# Updated_Schematic_11-13.net
KiCad netlist of a schematic drawn in EAGLE
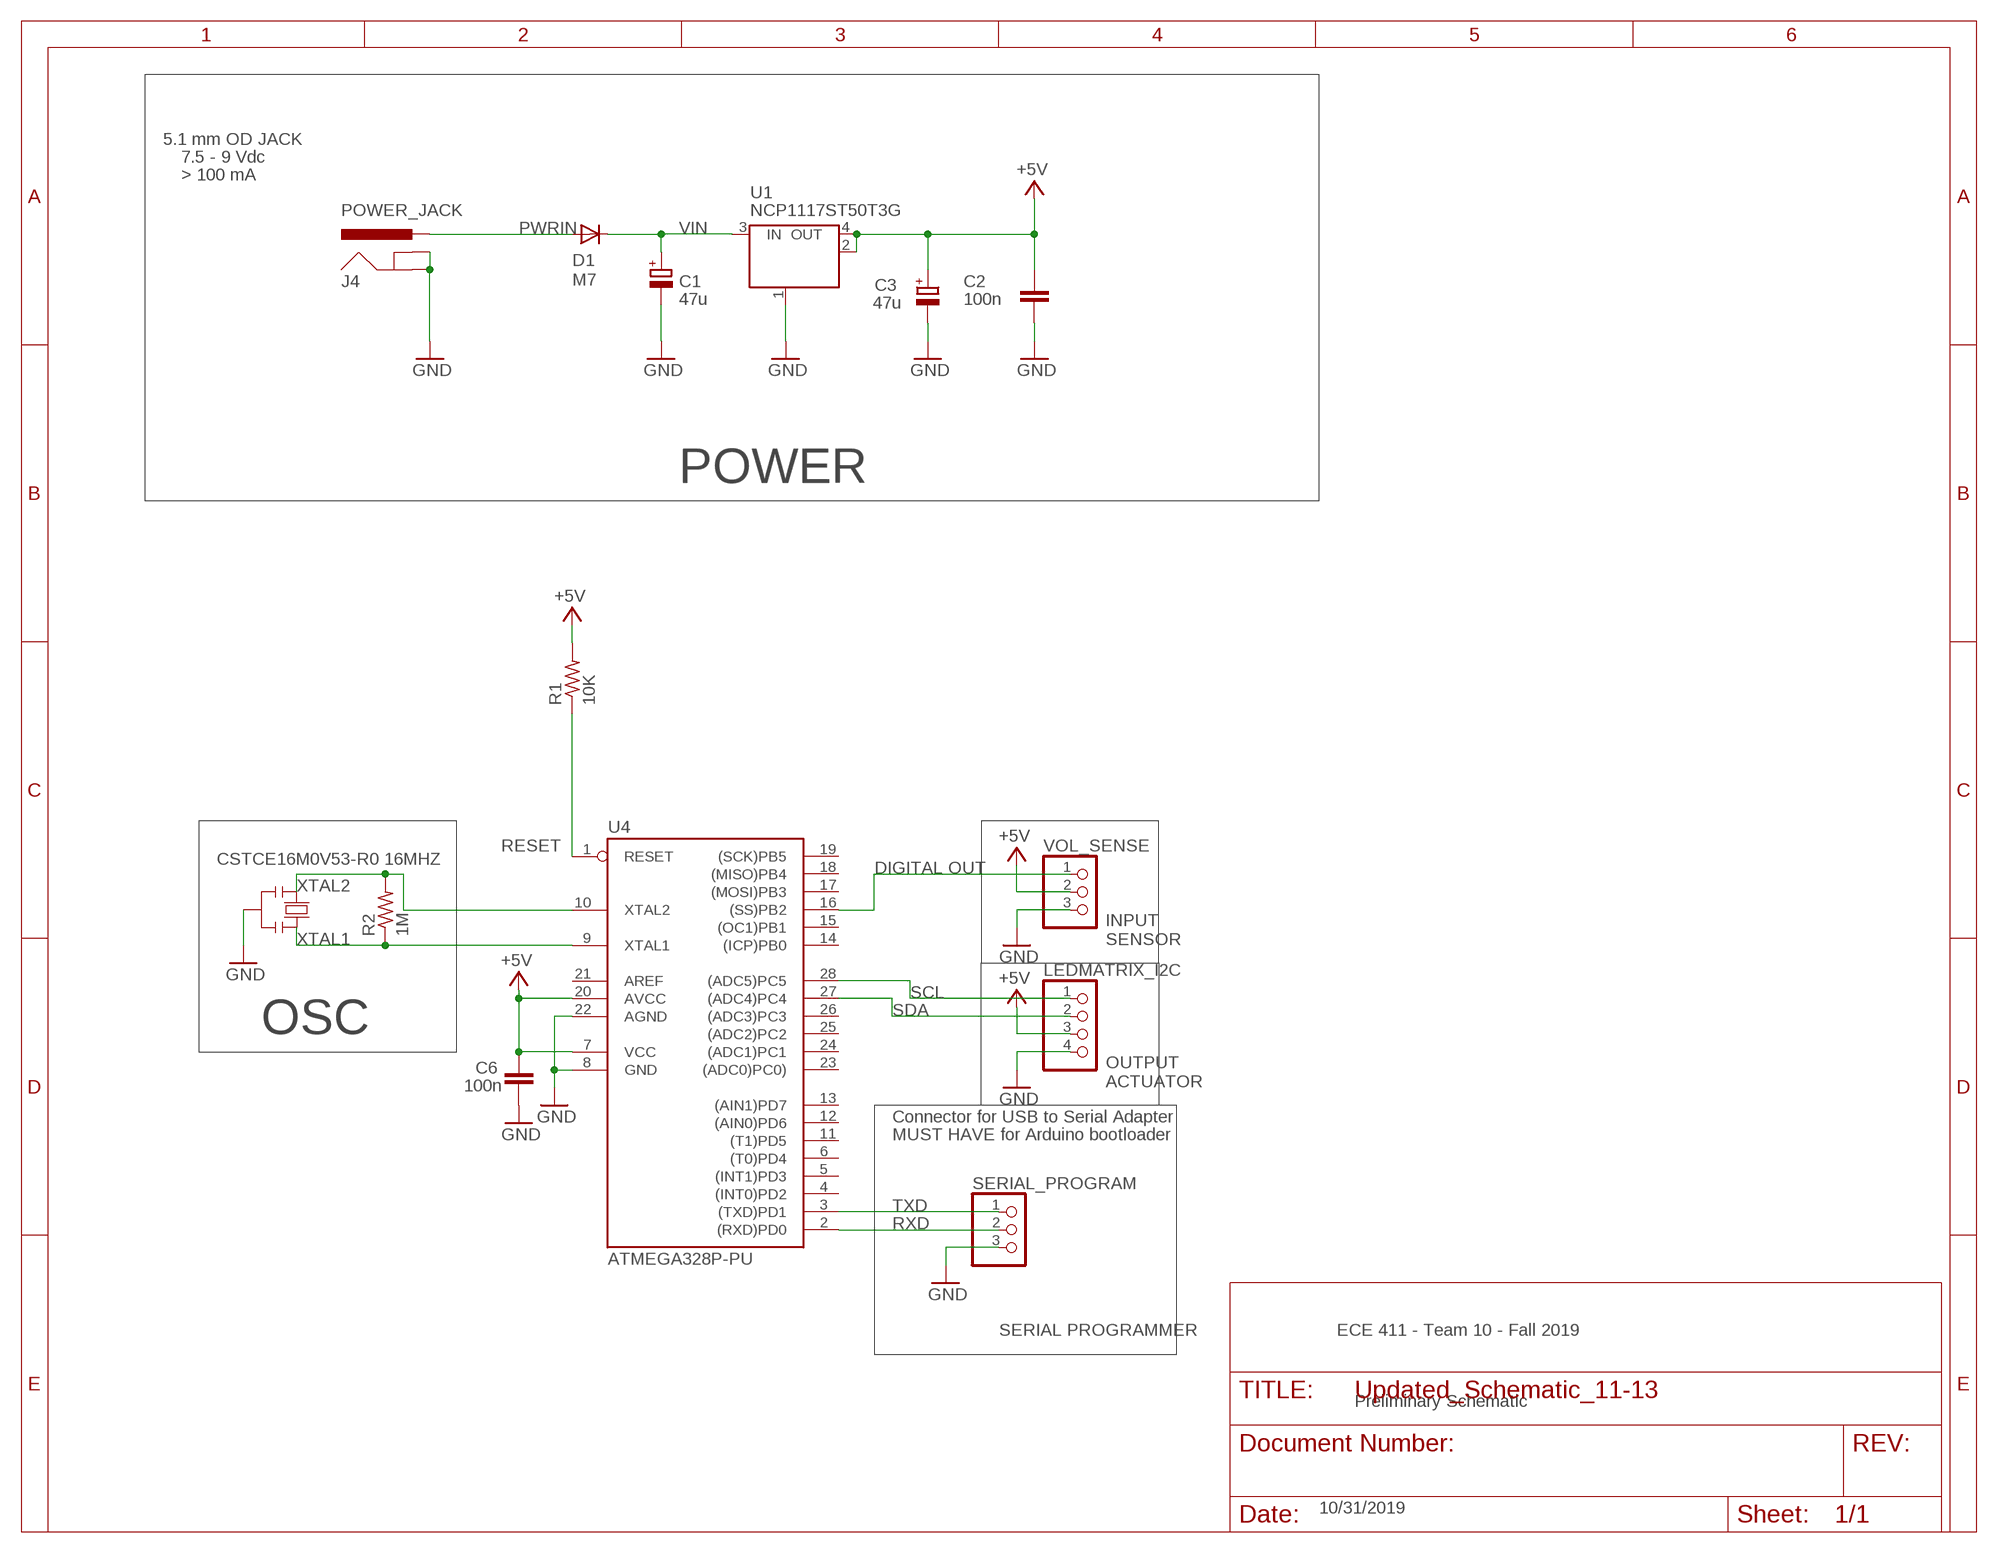
[diagram p0: schematic, sheet 1]

(export (version "E")
  (design (tool "Eeschema 10.0.6"))
  (components
    (comp (ref "C1")
      (value "47u")
      (footprint "eagle-import:PANASONIC_D")
      (libsource (lib "eagle-import") (part "CPOL-EUD"))
    )
    (comp (ref "C2")
      (value "100n")
      (footprint "eagle-import:C0805")
      (libsource (lib "eagle-import") (part "C-EUC0805"))
    )
    (comp (ref "C3")
      (value "47u")
      (footprint "eagle-import:PANASONIC_D")
      (libsource (lib "eagle-import") (part "CPOL-EUD"))
    )
    (comp (ref "C6")
      (value "100n")
      (footprint "eagle-import:C0805")
      (libsource (lib "eagle-import") (part "C-EUC0805"))
    )
    (comp (ref "D1")
      (value "M7")
      (footprint "eagle-import:SMB")
      (libsource (lib "eagle-import") (part "DIODE-SMB"))
    )
    (comp (ref "J4")
      (value "POWER_JACK")
      (footprint "eagle-import:POWER_JACK_PTH")
      (libsource (lib "eagle-import") (part "POWER_JACK"))
    )
    (comp (ref "LEDMATRIX_I2C")
      (value "PINHD-1X4")
      (footprint "eagle-import:1X04")
      (libsource (lib "eagle-import") (part "PINHD-1X4"))
    )
    (comp (ref "R1")
      (value "10K")
      (footprint "eagle-import:R0805")
      (libsource (lib "eagle-import") (part "R-US_R0805"))
    )
    (comp (ref "R2")
      (value "1M")
      (footprint "eagle-import:R0805")
      (libsource (lib "eagle-import") (part "R-US_R0805"))
    )
    (comp (ref "SERIAL_PROGRAM")
      (value "PINHD-1X3")
      (footprint "eagle-import:1X03")
      (libsource (lib "eagle-import") (part "PINHD-1X3"))
    )
    (comp (ref "U1")
      (value "NCP1117ST50T3G")
      (footprint "eagle-import:SOT223")
      (libsource (lib "eagle-import") (part "MC33269ST-3.3T3"))
    )
    (comp (ref "U4")
      (value "ATMEGA328P-PU")
      (footprint "eagle-import:DIL28-3")
      (libsource (lib "eagle-import") (part "ATMEGA328P-PU"))
    )
    (comp (ref "VOL_SENSE")
      (value "PINHD-1X3")
      (footprint "eagle-import:1X03")
      (libsource (lib "eagle-import") (part "PINHD-1X3"))
    )
    (comp (ref "X1")
      (value "CSTCE16M0V53-R0 16MHZ")
      (footprint "eagle-import:RESONATOR")
      (libsource (lib "eagle-import") (part "RESONATORMU"))
    )
  )
  (nets
    (net (code "1") (name "+5V") (class "Default")
      (node (ref "C2") (pin "2") (pinfunction "2_2") (pintype "passive"))
      (node (ref "C3") (pin "+") (pinfunction "+_+") (pintype "passive"))
      (node (ref "C6") (pin "2") (pinfunction "2_2") (pintype "passive"))
      (node (ref "LEDMATRIX_I2C") (pin "3") (pinfunction "3_3") (pintype "passive"))
      (node (ref "R1") (pin "2") (pinfunction "2_2") (pintype "passive"))
      (node (ref "U1") (pin "2") (pinfunction "OUT_2") (pintype "passive"))
      (node (ref "U1") (pin "4") (pinfunction "OUT_4") (pintype "passive"))
      (node (ref "U4") (pin "20") (pinfunction "AVCC_20") (pintype "power_in"))
      (node (ref "U4") (pin "7") (pinfunction "VCC_7") (pintype "power_in"))
      (node (ref "VOL_SENSE") (pin "2") (pinfunction "2_2") (pintype "passive"))
    )
    (net (code "2") (name "/PWRIN") (class "Default")
      (node (ref "D1") (pin "A") (pinfunction "A_A") (pintype "passive"))
      (node (ref "J4") (pin "PWR") (pinfunction "PWR_PWR") (pintype "bidirectional"))
    )
    (net (code "3") (name "/RESET") (class "Default")
      (node (ref "R1") (pin "1") (pinfunction "1_1") (pintype "passive"))
      (node (ref "U4") (pin "1") (pinfunction "RESET_1") (pintype "input"))
    )
    (net (code "4") (name "/RXD") (class "Default")
      (node (ref "SERIAL_PROGRAM") (pin "2") (pinfunction "2_2") (pintype "passive"))
      (node (ref "U4") (pin "2") (pinfunction "(RXD)PD0_2") (pintype "bidirectional"))
    )
    (net (code "5") (name "/SCL") (class "Default")
      (node (ref "LEDMATRIX_I2C") (pin "1") (pinfunction "1_1") (pintype "passive"))
      (node (ref "U4") (pin "28") (pinfunction "(ADC5)PC5_28") (pintype "bidirectional"))
    )
    (net (code "6") (name "/SDA") (class "Default")
      (node (ref "LEDMATRIX_I2C") (pin "2") (pinfunction "2_2") (pintype "passive"))
      (node (ref "U4") (pin "27") (pinfunction "(ADC4)PC4_27") (pintype "bidirectional"))
    )
    (net (code "7") (name "/TXD") (class "Default")
      (node (ref "SERIAL_PROGRAM") (pin "1") (pinfunction "1_1") (pintype "passive"))
      (node (ref "U4") (pin "3") (pinfunction "(TXD)PD1_3") (pintype "bidirectional"))
    )
    (net (code "8") (name "/VIN") (class "Default")
      (node (ref "C1") (pin "+") (pinfunction "+_+") (pintype "passive"))
      (node (ref "D1") (pin "C") (pinfunction "C_C") (pintype "passive"))
      (node (ref "U1") (pin "3") (pinfunction "IN_3") (pintype "input"))
    )
    (net (code "9") (name "/XTAL1") (class "Default")
      (node (ref "R2") (pin "1") (pinfunction "1_1") (pintype "passive"))
      (node (ref "U4") (pin "9") (pinfunction "XTAL1_9") (pintype "bidirectional"))
      (node (ref "X1") (pin "3") (pinfunction "3_3") (pintype "passive"))
    )
    (net (code "10") (name "/XTAL2") (class "Default")
      (node (ref "R2") (pin "2") (pinfunction "2_2") (pintype "passive"))
      (node (ref "U4") (pin "10") (pinfunction "XTAL2_10") (pintype "bidirectional"))
      (node (ref "X1") (pin "1") (pinfunction "1_1") (pintype "passive"))
    )
    (net (code "11") (name "GND") (class "Default")
      (node (ref "C1") (pin "-") (pinfunction "-_-") (pintype "passive"))
      (node (ref "C2") (pin "1") (pinfunction "1_1") (pintype "passive"))
      (node (ref "C3") (pin "-") (pinfunction "-_-") (pintype "passive"))
      (node (ref "C6") (pin "1") (pinfunction "1_1") (pintype "passive"))
      (node (ref "J4") (pin "GND") (pinfunction "GND_GND") (pintype "bidirectional"))
      (node (ref "J4") (pin "GNDBREAK") (pinfunction "GNDBREAK_GNDBREAK") (pintype "bidirectional"))
      (node (ref "LEDMATRIX_I2C") (pin "4") (pinfunction "4_4") (pintype "passive"))
      (node (ref "SERIAL_PROGRAM") (pin "3") (pinfunction "3_3") (pintype "passive"))
      (node (ref "U1") (pin "1") (pinfunction "GND/ADJ_1") (pintype "input"))
      (node (ref "U4") (pin "22") (pinfunction "AGND_22") (pintype "power_in"))
      (node (ref "U4") (pin "8") (pinfunction "GND_8") (pintype "power_in"))
      (node (ref "VOL_SENSE") (pin "3") (pinfunction "3_3") (pintype "passive"))
      (node (ref "X1") (pin "2") (pinfunction "2_2") (pintype "passive"))
    )
    (net (code "12") (name "Net-(U4-(SS)PB2)") (class "Default")
      (node (ref "U4") (pin "16") (pinfunction "(SS)PB2_16") (pintype "bidirectional"))
      (node (ref "VOL_SENSE") (pin "1") (pinfunction "1_1") (pintype "passive"))
    )
    (net (code "13") (name "unconnected-(U4-(ADC0)PC0)-Pad23)") (class "Default")
      (node (ref "U4") (pin "23") (pinfunction "(ADC0)PC0)_23") (pintype "bidirectional"))
    )
    (net (code "14") (name "unconnected-(U4-(ADC1)PC1-Pad24)") (class "Default")
      (node (ref "U4") (pin "24") (pinfunction "(ADC1)PC1_24") (pintype "bidirectional"))
    )
    (net (code "15") (name "unconnected-(U4-(ADC2)PC2-Pad25)") (class "Default")
      (node (ref "U4") (pin "25") (pinfunction "(ADC2)PC2_25") (pintype "bidirectional"))
    )
    (net (code "16") (name "unconnected-(U4-(ADC3)PC3-Pad26)") (class "Default")
      (node (ref "U4") (pin "26") (pinfunction "(ADC3)PC3_26") (pintype "bidirectional"))
    )
    (net (code "17") (name "unconnected-(U4-(AIN0)PD6-Pad12)") (class "Default")
      (node (ref "U4") (pin "12") (pinfunction "(AIN0)PD6_12") (pintype "bidirectional"))
    )
    (net (code "18") (name "unconnected-(U4-(AIN1)PD7-Pad13)") (class "Default")
      (node (ref "U4") (pin "13") (pinfunction "(AIN1)PD7_13") (pintype "bidirectional"))
    )
    (net (code "19") (name "unconnected-(U4-(ICP)PB0-Pad14)") (class "Default")
      (node (ref "U4") (pin "14") (pinfunction "(ICP)PB0_14") (pintype "bidirectional"))
    )
    (net (code "20") (name "unconnected-(U4-(INT0)PD2-Pad4)") (class "Default")
      (node (ref "U4") (pin "4") (pinfunction "(INT0)PD2_4") (pintype "bidirectional"))
    )
    (net (code "21") (name "unconnected-(U4-(INT1)PD3-Pad5)") (class "Default")
      (node (ref "U4") (pin "5") (pinfunction "(INT1)PD3_5") (pintype "bidirectional"))
    )
    (net (code "22") (name "unconnected-(U4-(MISO)PB4-Pad18)") (class "Default")
      (node (ref "U4") (pin "18") (pinfunction "(MISO)PB4_18") (pintype "bidirectional"))
    )
    (net (code "23") (name "unconnected-(U4-(MOSI)PB3-Pad17)") (class "Default")
      (node (ref "U4") (pin "17") (pinfunction "(MOSI)PB3_17") (pintype "bidirectional"))
    )
    (net (code "24") (name "unconnected-(U4-(OC1)PB1-Pad15)") (class "Default")
      (node (ref "U4") (pin "15") (pinfunction "(OC1)PB1_15") (pintype "bidirectional"))
    )
    (net (code "25") (name "unconnected-(U4-(SCK)PB5-Pad19)") (class "Default")
      (node (ref "U4") (pin "19") (pinfunction "(SCK)PB5_19") (pintype "bidirectional"))
    )
    (net (code "26") (name "unconnected-(U4-(T0)PD4-Pad6)") (class "Default")
      (node (ref "U4") (pin "6") (pinfunction "(T0)PD4_6") (pintype "bidirectional"))
    )
    (net (code "27") (name "unconnected-(U4-(T1)PD5-Pad11)") (class "Default")
      (node (ref "U4") (pin "11") (pinfunction "(T1)PD5_11") (pintype "bidirectional"))
    )
    (net (code "28") (name "unconnected-(U4-AREF-Pad21)") (class "Default")
      (node (ref "U4") (pin "21") (pinfunction "AREF_21") (pintype "passive"))
    )
  )
)
